# XU1541Mini.net
KiCad netlist of a schematic drawn in EAGLE
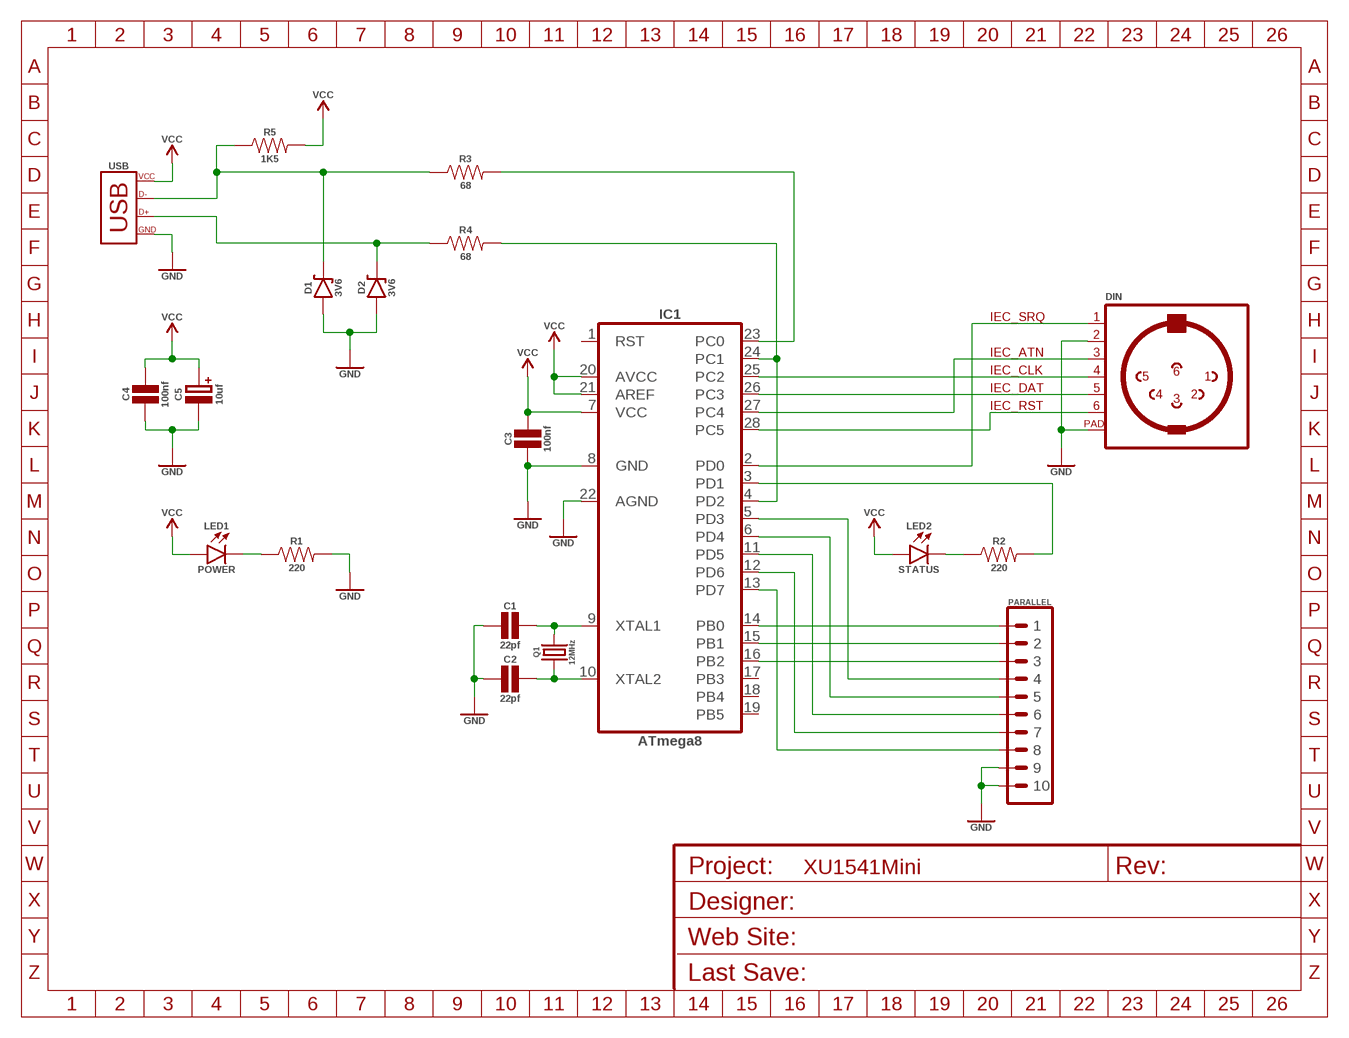
[diagram p0: schematic, sheet 1]

(export (version "E")
  (design (tool "Eeschema 10.0.6"))
  (components
    (comp (ref "C1")
      (value "22pf")
      (footprint "eagle-import:CAPACITOR_CERAMIC_0.1")
      (libsource (lib "eagle-import") (part "CAPACITOR_CERAMIC_0.1"))
    )
    (comp (ref "C2")
      (value "22pf")
      (footprint "eagle-import:CAPACITOR_CERAMIC_0.1")
      (libsource (lib "eagle-import") (part "CAPACITOR_CERAMIC_0.1"))
    )
    (comp (ref "C3")
      (value "100nf")
      (footprint "eagle-import:CAPACITOR_CERAMIC_0.1")
      (libsource (lib "eagle-import") (part "CAPACITOR_CERAMIC_0.1"))
    )
    (comp (ref "C4")
      (value "100nf")
      (footprint "eagle-import:CAPACITOR_CERAMIC_0.1")
      (libsource (lib "eagle-import") (part "CAPACITOR_CERAMIC_0.1"))
    )
    (comp (ref "C5")
      (value "10uf")
      (footprint "eagle-import:CAPACITOR_POLARIZED_0.1")
      (libsource (lib "eagle-import") (part "CAPACITOR_POLARIZED_0.1"))
    )
    (comp (ref "D1")
      (value "3V6")
      (footprint "eagle-import:DIODE_ZENER_0.3")
      (libsource (lib "eagle-import") (part "DIODE_ZENER_0.3"))
    )
    (comp (ref "D2")
      (value "3V6")
      (footprint "eagle-import:DIODE_ZENER_0.3")
      (libsource (lib "eagle-import") (part "DIODE_ZENER_0.3"))
    )
    (comp (ref "DIN")
      (value "DIN6")
      (footprint "eagle-import:DIN6")
      (libsource (lib "eagle-import") (part "DIN6"))
    )
    (comp (ref "IC1")
      (value "ATmega8")
      (footprint "eagle-import:DIP28")
      (libsource (lib "eagle-import") (part "MCU_ATMEGA8-16PU"))
    )
    (comp (ref "JP1")
      (value "PARALLEL")
      (footprint "eagle-import:HDR_2X05")
      (libsource (lib "eagle-import") (part "HDR_2X05"))
    )
    (comp (ref "LED1")
      (value "POWER")
      (footprint "eagle-import:LED_03MM")
      (libsource (lib "eagle-import") (part "LED_NORMAL_03MM"))
    )
    (comp (ref "LED2")
      (value "STATUS")
      (footprint "eagle-import:LED_03MM")
      (libsource (lib "eagle-import") (part "LED_NORMAL_03MM"))
    )
    (comp (ref "Q1")
      (value "12MHz")
      (footprint "eagle-import:XTAL_HC49")
      (libsource (lib "eagle-import") (part "XTAL_HC49"))
    )
    (comp (ref "R1")
      (value "220")
      (footprint "eagle-import:RESISTOR_THT_0.3")
      (libsource (lib "eagle-import") (part "RESISTOR_THT_0.3"))
    )
    (comp (ref "R2")
      (value "220")
      (footprint "eagle-import:RESISTOR_THT_0.3")
      (libsource (lib "eagle-import") (part "RESISTOR_THT_0.3"))
    )
    (comp (ref "R3")
      (value "68")
      (footprint "eagle-import:RESISTOR_THT_0.3")
      (libsource (lib "eagle-import") (part "RESISTOR_THT_0.3"))
    )
    (comp (ref "R4")
      (value "68")
      (footprint "eagle-import:RESISTOR_THT_0.3")
      (libsource (lib "eagle-import") (part "RESISTOR_THT_0.3"))
    )
    (comp (ref "R5")
      (value "1K5")
      (footprint "eagle-import:RESISTOR_THT_0.3")
      (libsource (lib "eagle-import") (part "RESISTOR_THT_0.3"))
    )
    (comp (ref "USB")
      (value "USB_TYPEB_THT")
      (footprint "eagle-import:USB_TYPEB_THT")
      (libsource (lib "eagle-import") (part "USB_TYPEB_THT"))
    )
  )
  (nets
    (net (code "1") (name "GND") (class "Default")
      (node (ref "C1") (pin "1") (pinfunction "1_1") (pintype "passive"))
      (node (ref "C2") (pin "1") (pinfunction "1_1") (pintype "passive"))
      (node (ref "C3") (pin "1") (pinfunction "1_1") (pintype "passive"))
      (node (ref "C4") (pin "1") (pinfunction "1_1") (pintype "passive"))
      (node (ref "C5") (pin "2") (pinfunction "-_2") (pintype "passive"))
      (node (ref "D1") (pin "A") (pinfunction "ANODE_A") (pintype "passive"))
      (node (ref "D2") (pin "A") (pinfunction "ANODE_A") (pintype "passive"))
      (node (ref "DIN") (pin "2") (pinfunction "2_2") (pintype "passive"))
      (node (ref "DIN") (pin "PAD@1") (pinfunction "PAD_PAD@1") (pintype "passive"))
      (node (ref "DIN") (pin "PAD@2") (pinfunction "PAD_PAD@2") (pintype "passive"))
      (node (ref "IC1") (pin "22") (pinfunction "AGND_22") (pintype "passive"))
      (node (ref "IC1") (pin "8") (pinfunction "GND_8") (pintype "power_in"))
      (node (ref "JP1") (pin "10") (pinfunction "10_10") (pintype "passive"))
      (node (ref "JP1") (pin "9") (pinfunction "9_9") (pintype "passive"))
      (node (ref "R1") (pin "2") (pinfunction "2_2") (pintype "passive"))
      (node (ref "USB") (pin "GND") (pinfunction "GND_GND") (pintype "bidirectional"))
      (node (ref "USB") (pin "PAD@1") (pinfunction "GND_PAD@1") (pintype "bidirectional"))
      (node (ref "USB") (pin "PAD@2") (pinfunction "GND_PAD@2") (pintype "bidirectional"))
    )
    (net (code "2") (name "Net-(D1-CATHODE)") (class "Default")
      (node (ref "D1") (pin "C") (pinfunction "CATHODE_C") (pintype "passive"))
      (node (ref "R3") (pin "1") (pinfunction "1_1") (pintype "passive"))
      (node (ref "R5") (pin "1") (pinfunction "1_1") (pintype "passive"))
      (node (ref "USB") (pin "D-") (pinfunction "D-_D-") (pintype "bidirectional"))
    )
    (net (code "3") (name "Net-(D2-CATHODE)") (class "Default")
      (node (ref "D2") (pin "C") (pinfunction "CATHODE_C") (pintype "passive"))
      (node (ref "R4") (pin "1") (pinfunction "1_1") (pintype "passive"))
      (node (ref "USB") (pin "D+") (pinfunction "D+_D+") (pintype "bidirectional"))
    )
    (net (code "4") (name "Net-(IC1-PB0)") (class "Default")
      (node (ref "IC1") (pin "14") (pinfunction "PB0_14") (pintype "bidirectional"))
      (node (ref "JP1") (pin "1") (pinfunction "1_1") (pintype "passive"))
    )
    (net (code "5") (name "Net-(IC1-PB1)") (class "Default")
      (node (ref "IC1") (pin "15") (pinfunction "PB1_15") (pintype "bidirectional"))
      (node (ref "JP1") (pin "2") (pinfunction "2_2") (pintype "passive"))
    )
    (net (code "6") (name "Net-(IC1-PB2)") (class "Default")
      (node (ref "IC1") (pin "16") (pinfunction "PB2_16") (pintype "bidirectional"))
      (node (ref "JP1") (pin "3") (pinfunction "3_3") (pintype "passive"))
    )
    (net (code "7") (name "Net-(IC1-PC0)") (class "Default")
      (node (ref "IC1") (pin "23") (pinfunction "PC0_23") (pintype "bidirectional"))
      (node (ref "R3") (pin "2") (pinfunction "2_2") (pintype "passive"))
    )
    (net (code "8") (name "Net-(IC1-PC1)") (class "Default")
      (node (ref "IC1") (pin "24") (pinfunction "PC1_24") (pintype "bidirectional"))
      (node (ref "IC1") (pin "4") (pinfunction "PD2_4") (pintype "bidirectional"))
      (node (ref "R4") (pin "2") (pinfunction "2_2") (pintype "passive"))
    )
    (net (code "9") (name "Net-(IC1-PC2)") (class "Default")
      (node (ref "DIN") (pin "4") (pinfunction "4_4") (pintype "passive"))
      (node (ref "IC1") (pin "25") (pinfunction "PC2_25") (pintype "bidirectional"))
    )
    (net (code "10") (name "Net-(IC1-PC3)") (class "Default")
      (node (ref "DIN") (pin "5") (pinfunction "5_5") (pintype "passive"))
      (node (ref "IC1") (pin "26") (pinfunction "PC3_26") (pintype "bidirectional"))
    )
    (net (code "11") (name "Net-(IC1-PC4)") (class "Default")
      (node (ref "DIN") (pin "3") (pinfunction "3_3") (pintype "passive"))
      (node (ref "IC1") (pin "27") (pinfunction "PC4_27") (pintype "bidirectional"))
    )
    (net (code "12") (name "Net-(IC1-PC5)") (class "Default")
      (node (ref "DIN") (pin "6") (pinfunction "6_6") (pintype "passive"))
      (node (ref "IC1") (pin "28") (pinfunction "PC5_28") (pintype "bidirectional"))
    )
    (net (code "13") (name "Net-(IC1-PD0)") (class "Default")
      (node (ref "DIN") (pin "1") (pinfunction "1_1") (pintype "passive"))
      (node (ref "IC1") (pin "2") (pinfunction "PD0_2") (pintype "bidirectional"))
    )
    (net (code "14") (name "Net-(IC1-PD1)") (class "Default")
      (node (ref "IC1") (pin "3") (pinfunction "PD1_3") (pintype "bidirectional"))
      (node (ref "R2") (pin "2") (pinfunction "2_2") (pintype "passive"))
    )
    (net (code "15") (name "Net-(IC1-PD3)") (class "Default")
      (node (ref "IC1") (pin "5") (pinfunction "PD3_5") (pintype "bidirectional"))
      (node (ref "JP1") (pin "4") (pinfunction "4_4") (pintype "passive"))
    )
    (net (code "16") (name "Net-(IC1-PD4)") (class "Default")
      (node (ref "IC1") (pin "6") (pinfunction "PD4_6") (pintype "bidirectional"))
      (node (ref "JP1") (pin "5") (pinfunction "5_5") (pintype "passive"))
    )
    (net (code "17") (name "Net-(IC1-PD5)") (class "Default")
      (node (ref "IC1") (pin "11") (pinfunction "PD5_11") (pintype "bidirectional"))
      (node (ref "JP1") (pin "6") (pinfunction "6_6") (pintype "passive"))
    )
    (net (code "18") (name "Net-(IC1-PD6)") (class "Default")
      (node (ref "IC1") (pin "12") (pinfunction "PD6_12") (pintype "bidirectional"))
      (node (ref "JP1") (pin "7") (pinfunction "7_7") (pintype "passive"))
    )
    (net (code "19") (name "Net-(IC1-PD7)") (class "Default")
      (node (ref "IC1") (pin "13") (pinfunction "PD7_13") (pintype "bidirectional"))
      (node (ref "JP1") (pin "8") (pinfunction "8_8") (pintype "passive"))
    )
    (net (code "20") (name "Net-(IC1-XTAL1)") (class "Default")
      (node (ref "C1") (pin "2") (pinfunction "2_2") (pintype "passive"))
      (node (ref "IC1") (pin "9") (pinfunction "XTAL1_9") (pintype "bidirectional"))
      (node (ref "Q1") (pin "2") (pinfunction "2_2") (pintype "passive"))
    )
    (net (code "21") (name "Net-(IC1-XTAL2)") (class "Default")
      (node (ref "C2") (pin "2") (pinfunction "2_2") (pintype "passive"))
      (node (ref "IC1") (pin "10") (pinfunction "XTAL2_10") (pintype "bidirectional"))
      (node (ref "Q1") (pin "1") (pinfunction "1_1") (pintype "passive"))
    )
    (net (code "22") (name "Net-(LED1-C)") (class "Default")
      (node (ref "LED1") (pin "CATHODE") (pinfunction "C_CATHODE") (pintype "passive"))
      (node (ref "R1") (pin "1") (pinfunction "1_1") (pintype "passive"))
    )
    (net (code "23") (name "Net-(LED2-C)") (class "Default")
      (node (ref "LED2") (pin "CATHODE") (pinfunction "C_CATHODE") (pintype "passive"))
      (node (ref "R2") (pin "1") (pinfunction "1_1") (pintype "passive"))
    )
    (net (code "24") (name "VCC") (class "Default")
      (node (ref "C3") (pin "2") (pinfunction "2_2") (pintype "passive"))
      (node (ref "C4") (pin "2") (pinfunction "2_2") (pintype "passive"))
      (node (ref "C5") (pin "1") (pinfunction "+_1") (pintype "passive"))
      (node (ref "IC1") (pin "20") (pinfunction "AVCC_20") (pintype "passive"))
      (node (ref "IC1") (pin "21") (pinfunction "AREF_21") (pintype "passive"))
      (node (ref "IC1") (pin "7") (pinfunction "VCC_7") (pintype "power_in"))
      (node (ref "LED1") (pin "ANODE") (pinfunction "A_ANODE") (pintype "passive"))
      (node (ref "LED2") (pin "ANODE") (pinfunction "A_ANODE") (pintype "passive"))
      (node (ref "R5") (pin "2") (pinfunction "2_2") (pintype "passive"))
      (node (ref "USB") (pin "VCC") (pinfunction "VCC_VCC") (pintype "bidirectional"))
    )
    (net (code "25") (name "unconnected-(IC1-PB3-Pad17)") (class "Default")
      (node (ref "IC1") (pin "17") (pinfunction "PB3_17") (pintype "bidirectional"))
    )
    (net (code "26") (name "unconnected-(IC1-PB4-Pad18)") (class "Default")
      (node (ref "IC1") (pin "18") (pinfunction "PB4_18") (pintype "bidirectional"))
    )
    (net (code "27") (name "unconnected-(IC1-PB5-Pad19)") (class "Default")
      (node (ref "IC1") (pin "19") (pinfunction "PB5_19") (pintype "bidirectional"))
    )
    (net (code "28") (name "unconnected-(IC1-RST-Pad1)") (class "Default")
      (node (ref "IC1") (pin "1") (pinfunction "RST_1") (pintype "bidirectional"))
    )
  )
)
